# Relay_Latches.net
KiCad netlist of a schematic drawn in Altium Designer
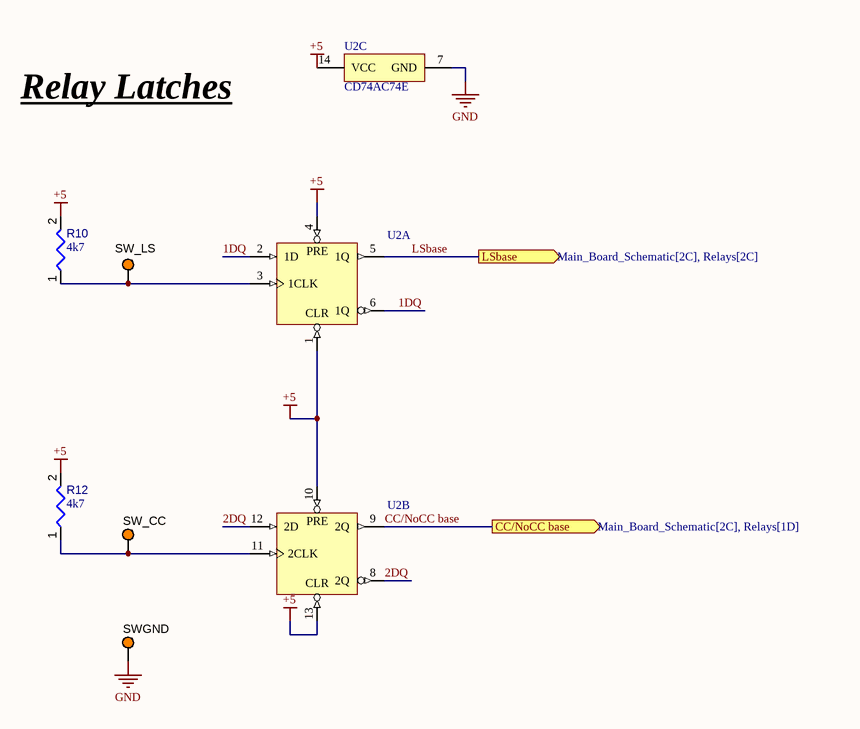
[diagram p0: Relay_Latches.SchDoc]

(export (version "E")
  (design (tool "Eeschema 10.0.6"))
  (components
    (comp (ref "R10")
      (value "4k7")
      (footprint "RESA60-630X240")
      (description "Axial Resistor, 100 Ohm, +/- 1%, 0.25 W, -55 to 155 degC, 2-Pin THD, RoHS, Bulk")
      (fields (field (name "MANUFACTURER") "Yageo") (field (name "TOLERANCE") "1%"))
      (libsource (lib "Konstantinos Psarras") (part "RES-2"))
    )
    (comp (ref "R12")
      (value "4k7")
      (footprint "RESA60-630X240")
      (description "Axial Resistor, 100 Ohm, +/- 1%, 0.25 W, -55 to 155 degC, 2-Pin THD, RoHS, Bulk")
      (fields (field (name "MANUFACTURER") "Yageo") (field (name "TOLERANCE") "1%"))
      (libsource (lib "Konstantinos Psarras") (part "RES-2"))
    )
    (comp (ref "SWGND")
      (value "5003")
      (footprint "KSTN-5003")
      (description "Test Point, Orange, Height 4.6 mm, Tail Length 3 mm, 1-Pin THD, RoHS")
      (fields (field (name "MANUFACTURER") "Keystone"))
      (libsource (lib "Konstantinos Psarras") (part "TESTPOINT_ORANGE"))
    )
    (comp (ref "SW_CC")
      (value "5003")
      (footprint "KSTN-5003")
      (description "Test Point, Orange, Height 4.6 mm, Tail Length 3 mm, 1-Pin THD, RoHS")
      (fields (field (name "MANUFACTURER") "Keystone"))
      (libsource (lib "Konstantinos Psarras") (part "TESTPOINT_ORANGE"))
    )
    (comp (ref "SW_LS")
      (value "5003")
      (footprint "KSTN-5003")
      (description "Test Point, Orange, Height 4.6 mm, Tail Length 3 mm, 1-Pin THD, RoHS")
      (fields (field (name "MANUFACTURER") "Keystone"))
      (libsource (lib "Konstantinos Psarras") (part "TESTPOINT_ORANGE"))
    )
    (comp (ref "U2")
      (value "CD74AC74E")
      (footprint "N0014A")
      (description "Dual Positive-Edge-Triggered D-Type Flip-Flops with Set and Reset, N0014A, TUBE")
      (fields
        (field (name "GENERIC PART NUMBER") "CD74AC74")
        (field (name "MANUFACTURER") "Texas Instruments")
      )
      (libsource (lib "Altium Content Vault") (part "TI-CD_SNX4XXXX74X-14"))
    )
  )
  (nets
    (net (code "1") (name "+5") (class "Default")
      (node (ref "R10") (pin "2") (pinfunction "2_2") (pintype "passive"))
      (node (ref "R12") (pin "2") (pinfunction "2_2") (pintype "passive"))
      (node (ref "U2") (pin "1") (pinfunction "1~{CLR}_1") (pintype "input"))
      (node (ref "U2") (pin "10") (pinfunction "2~{PRE}_10") (pintype "input"))
      (node (ref "U2") (pin "13") (pinfunction "2~{CLR}_13") (pintype "input"))
      (node (ref "U2") (pin "14") (pinfunction "VCC_14") (pintype "power_in"))
      (node (ref "U2") (pin "4") (pinfunction "1~{PRE}_4") (pintype "input"))
    )
    (net (code "2") (name "/1DQ") (class "Default")
      (node (ref "U2") (pin "2") (pinfunction "1D_2") (pintype "input"))
      (node (ref "U2") (pin "6") (pinfunction "1Q_6") (pintype "output"))
    )
    (net (code "3") (name "/2DQ") (class "Default")
      (node (ref "U2") (pin "12") (pinfunction "2D_12") (pintype "input"))
      (node (ref "U2") (pin "8") (pinfunction "2Q_8") (pintype "output"))
    )
    (net (code "4") (name "/CC{slash}NoCC base") (class "Default")
      (node (ref "U2") (pin "9") (pinfunction "2Q_9") (pintype "output"))
    )
    (net (code "5") (name "/LSbase") (class "Default")
      (node (ref "U2") (pin "5") (pinfunction "1Q_5") (pintype "output"))
    )
    (net (code "6") (name "GND") (class "Default")
      (node (ref "SWGND") (pin "1") (pinfunction "1_1") (pintype "passive"))
      (node (ref "U2") (pin "7") (pinfunction "GND_7") (pintype "power_in"))
    )
    (net (code "7") (name "Net-(U2A-1CLK)") (class "Default")
      (node (ref "R10") (pin "1") (pinfunction "1_1") (pintype "passive"))
      (node (ref "SW_LS") (pin "1") (pinfunction "1_1") (pintype "passive"))
      (node (ref "U2") (pin "3") (pinfunction "1CLK_3") (pintype "input"))
    )
    (net (code "8") (name "Net-(U2B-2CLK)") (class "Default")
      (node (ref "R12") (pin "1") (pinfunction "1_1") (pintype "passive"))
      (node (ref "SW_CC") (pin "1") (pinfunction "1_1") (pintype "passive"))
      (node (ref "U2") (pin "11") (pinfunction "2CLK_11") (pintype "input"))
    )
  )
)
